# RS485_Mayfly.net
KiCad netlist of a schematic drawn in EAGLE
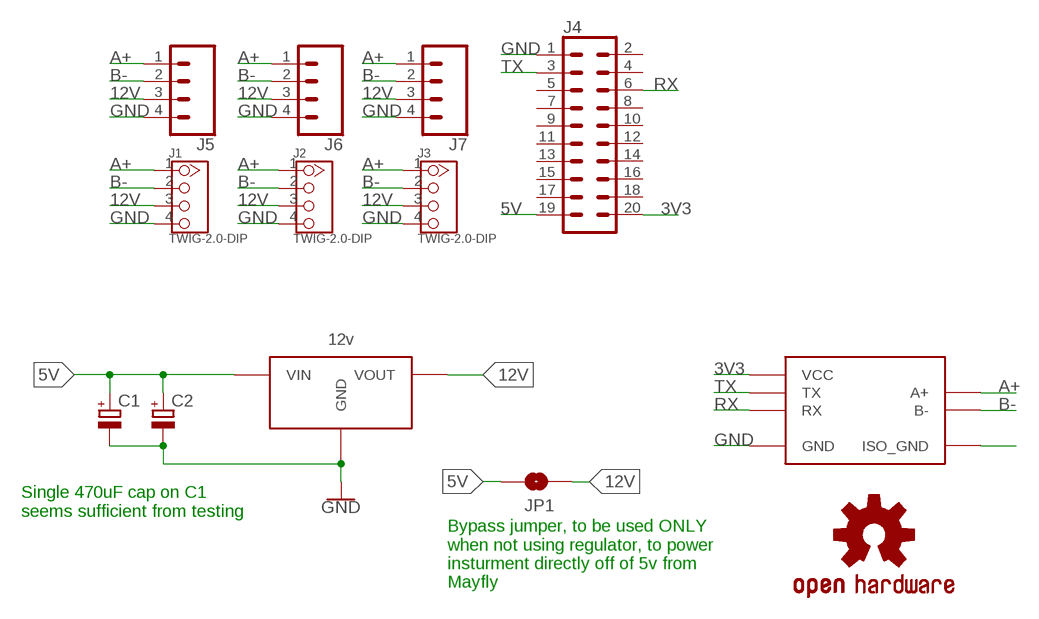
[diagram p0: schematic, sheet 1]

(export (version "E")
  (design (tool "Eeschema 10.0.6"))
  (components
    (comp (ref "C1")
      (value "CPOL-EUE2,5-6E")
      (footprint "eagle-import:E2,5-6E")
      (libsource (lib "eagle-import") (part "CPOL-EUE2,5-6E"))
    )
    (comp (ref "C2")
      (value "CPOL-EUE2,5-6E")
      (footprint "eagle-import:E2,5-6E")
      (libsource (lib "eagle-import") (part "CPOL-EUE2,5-6E"))
    )
    (comp (ref "J1")
      (value "TWIG-2.0-DIP")
      (footprint "eagle-import:2.0_1X4")
      (libsource (lib "eagle-import") (part "TWIG-2.0-DIP"))
    )
    (comp (ref "J2")
      (value "TWIG-2.0-DIP")
      (footprint "eagle-import:2.0_1X4")
      (libsource (lib "eagle-import") (part "TWIG-2.0-DIP"))
    )
    (comp (ref "J3")
      (value "TWIG-2.0-DIP")
      (footprint "eagle-import:2.0_1X4")
      (libsource (lib "eagle-import") (part "TWIG-2.0-DIP"))
    )
    (comp (ref "J4")
      (value "CONN_10X2MALE")
      (footprint "eagle-import:2X10")
      (fields (field (name "MF") "Sullins") (field (name "MPN") "PRPC010DAAN-RC"))
      (libsource (lib "eagle-import") (part "CONN_10X2MALE"))
    )
    (comp (ref "J5")
      (value "CONN_42.54_NOSILK")
      (footprint "eagle-import:1X04_NOSILK")
      (libsource (lib "eagle-import") (part "CONN_42.54_NOSILK"))
    )
    (comp (ref "J6")
      (value "CONN_42.54_NOSILK")
      (footprint "eagle-import:1X04_NOSILK")
      (libsource (lib "eagle-import") (part "CONN_42.54_NOSILK"))
    )
    (comp (ref "J7")
      (value "CONN_42.54_NOSILK")
      (footprint "eagle-import:1X04_NOSILK")
      (libsource (lib "eagle-import") (part "CONN_42.54_NOSILK"))
    )
    (comp (ref "JP1")
      (value "JUMPER-SMT_2_NO_SILK")
      (footprint "eagle-import:SMT-JUMPER_2_NO_SILK")
      (libsource (lib "eagle-import") (part "JUMPER-SMT_2_NO_SILK"))
    )
    (comp (ref "LOGO1")
      (value "OSHW-LOGOMINI")
      (footprint "eagle-import:OSHW-LOGO-MINI")
      (libsource (lib "eagle-import") (part "OSHW-LOGOMINI"))
    )
    (comp (ref "U$1")
      (value "12v")
      (footprint "eagle-import:POLOLU_REG")
      (libsource (lib "eagle-import") (part "POLOLU_VREG"))
    )
    (comp (ref "U$2")
      (value "SMC_RS485")
      (footprint "eagle-import:SMC_RS485")
      (libsource (lib "eagle-import") (part "SMC_RS485"))
    )
  )
  (nets
    (net (code "1") (name "/3V3") (class "Default")
      (node (ref "J4") (pin "20") (pinfunction "20_20") (pintype "passive"))
      (node (ref "U$2") (pin "VCC") (pinfunction "VCC_VCC") (pintype "bidirectional"))
    )
    (net (code "2") (name "/A+") (class "Default")
      (node (ref "J1") (pin "1") (pinfunction "1_1") (pintype "bidirectional"))
      (node (ref "J2") (pin "1") (pinfunction "1_1") (pintype "bidirectional"))
      (node (ref "J3") (pin "1") (pinfunction "1_1") (pintype "bidirectional"))
      (node (ref "J5") (pin "1") (pinfunction "1_1") (pintype "passive"))
      (node (ref "J6") (pin "1") (pinfunction "1_1") (pintype "passive"))
      (node (ref "J7") (pin "1") (pinfunction "1_1") (pintype "passive"))
      (node (ref "U$2") (pin "A+") (pinfunction "A+_A+") (pintype "bidirectional"))
    )
    (net (code "3") (name "/B-") (class "Default")
      (node (ref "J1") (pin "2") (pinfunction "2_2") (pintype "bidirectional"))
      (node (ref "J2") (pin "2") (pinfunction "2_2") (pintype "bidirectional"))
      (node (ref "J3") (pin "2") (pinfunction "2_2") (pintype "bidirectional"))
      (node (ref "J5") (pin "2") (pinfunction "2_2") (pintype "passive"))
      (node (ref "J6") (pin "2") (pinfunction "2_2") (pintype "passive"))
      (node (ref "J7") (pin "2") (pinfunction "2_2") (pintype "passive"))
      (node (ref "U$2") (pin "B-") (pinfunction "B-_B-") (pintype "bidirectional"))
    )
    (net (code "4") (name "/RX") (class "Default")
      (node (ref "J4") (pin "6") (pinfunction "6_6") (pintype "passive"))
      (node (ref "U$2") (pin "RX") (pinfunction "RX_RX") (pintype "bidirectional"))
    )
    (net (code "5") (name "/TX") (class "Default")
      (node (ref "J4") (pin "3") (pinfunction "3_3") (pintype "passive"))
      (node (ref "U$2") (pin "TX") (pinfunction "TX_TX") (pintype "bidirectional"))
    )
    (net (code "6") (name "5V") (class "Default")
      (node (ref "C1") (pin "+") (pinfunction "+_+") (pintype "passive"))
      (node (ref "C2") (pin "+") (pinfunction "+_+") (pintype "passive"))
      (node (ref "J4") (pin "19") (pinfunction "19_19") (pintype "passive"))
      (node (ref "JP1") (pin "2") (pinfunction "2_2") (pintype "passive"))
      (node (ref "U$1") (pin "VIN") (pinfunction "VIN_VIN") (pintype "bidirectional"))
    )
    (net (code "7") (name "12V") (class "Default")
      (node (ref "J1") (pin "3") (pinfunction "3_3") (pintype "bidirectional"))
      (node (ref "J2") (pin "3") (pinfunction "3_3") (pintype "bidirectional"))
      (node (ref "J3") (pin "3") (pinfunction "3_3") (pintype "bidirectional"))
      (node (ref "J5") (pin "3") (pinfunction "3_3") (pintype "passive"))
      (node (ref "J6") (pin "3") (pinfunction "3_3") (pintype "passive"))
      (node (ref "J7") (pin "3") (pinfunction "3_3") (pintype "passive"))
      (node (ref "JP1") (pin "1") (pinfunction "1_1") (pintype "passive"))
      (node (ref "U$1") (pin "VOUT") (pinfunction "VOUT_VOUT") (pintype "bidirectional"))
    )
    (net (code "8") (name "GND") (class "Default")
      (node (ref "C1") (pin "-") (pinfunction "-_-") (pintype "passive"))
      (node (ref "C2") (pin "-") (pinfunction "-_-") (pintype "passive"))
      (node (ref "J1") (pin "4") (pinfunction "4_4") (pintype "bidirectional"))
      (node (ref "J2") (pin "4") (pinfunction "4_4") (pintype "bidirectional"))
      (node (ref "J3") (pin "4") (pinfunction "4_4") (pintype "bidirectional"))
      (node (ref "J4") (pin "1") (pinfunction "1_1") (pintype "passive"))
      (node (ref "J5") (pin "4") (pinfunction "4_4") (pintype "passive"))
      (node (ref "J6") (pin "4") (pinfunction "4_4") (pintype "passive"))
      (node (ref "J7") (pin "4") (pinfunction "4_4") (pintype "passive"))
      (node (ref "U$1") (pin "GND") (pinfunction "GND_GND") (pintype "bidirectional"))
      (node (ref "U$2") (pin "GND") (pinfunction "GND_GND") (pintype "bidirectional"))
    )
    (net (code "9") (name "unconnected-(J4-Pad2)") (class "Default")
      (node (ref "J4") (pin "2") (pinfunction "2_2") (pintype "passive"))
    )
    (net (code "10") (name "unconnected-(J4-Pad4)") (class "Default")
      (node (ref "J4") (pin "4") (pinfunction "4_4") (pintype "passive"))
    )
    (net (code "11") (name "unconnected-(J4-Pad5)") (class "Default")
      (node (ref "J4") (pin "5") (pinfunction "5_5") (pintype "passive"))
    )
    (net (code "12") (name "unconnected-(J4-Pad7)") (class "Default")
      (node (ref "J4") (pin "7") (pinfunction "7_7") (pintype "passive"))
    )
    (net (code "13") (name "unconnected-(J4-Pad8)") (class "Default")
      (node (ref "J4") (pin "8") (pinfunction "8_8") (pintype "passive"))
    )
    (net (code "14") (name "unconnected-(J4-Pad9)") (class "Default")
      (node (ref "J4") (pin "9") (pinfunction "9_9") (pintype "passive"))
    )
    (net (code "15") (name "unconnected-(J4-Pad10)") (class "Default")
      (node (ref "J4") (pin "10") (pinfunction "10_10") (pintype "passive"))
    )
    (net (code "16") (name "unconnected-(J4-Pad11)") (class "Default")
      (node (ref "J4") (pin "11") (pinfunction "11_11") (pintype "passive"))
    )
    (net (code "17") (name "unconnected-(J4-Pad12)") (class "Default")
      (node (ref "J4") (pin "12") (pinfunction "12_12") (pintype "passive"))
    )
    (net (code "18") (name "unconnected-(J4-Pad13)") (class "Default")
      (node (ref "J4") (pin "13") (pinfunction "13_13") (pintype "passive"))
    )
    (net (code "19") (name "unconnected-(J4-Pad14)") (class "Default")
      (node (ref "J4") (pin "14") (pinfunction "14_14") (pintype "passive"))
    )
    (net (code "20") (name "unconnected-(J4-Pad15)") (class "Default")
      (node (ref "J4") (pin "15") (pinfunction "15_15") (pintype "passive"))
    )
    (net (code "21") (name "unconnected-(J4-Pad16)") (class "Default")
      (node (ref "J4") (pin "16") (pinfunction "16_16") (pintype "passive"))
    )
    (net (code "22") (name "unconnected-(J4-Pad17)") (class "Default")
      (node (ref "J4") (pin "17") (pinfunction "17_17") (pintype "passive"))
    )
    (net (code "23") (name "unconnected-(J4-Pad18)") (class "Default")
      (node (ref "J4") (pin "18") (pinfunction "18_18") (pintype "passive"))
    )
    (net (code "24") (name "unconnected-(U$2-ISO_GND-PadGND_ISO)") (class "Default")
      (node (ref "U$2") (pin "GND_ISO") (pinfunction "ISO_GND_GND_ISO") (pintype "bidirectional"))
    )
  )
)
